# MultiVS.net
KiCad netlist of a schematic drawn in EAGLE
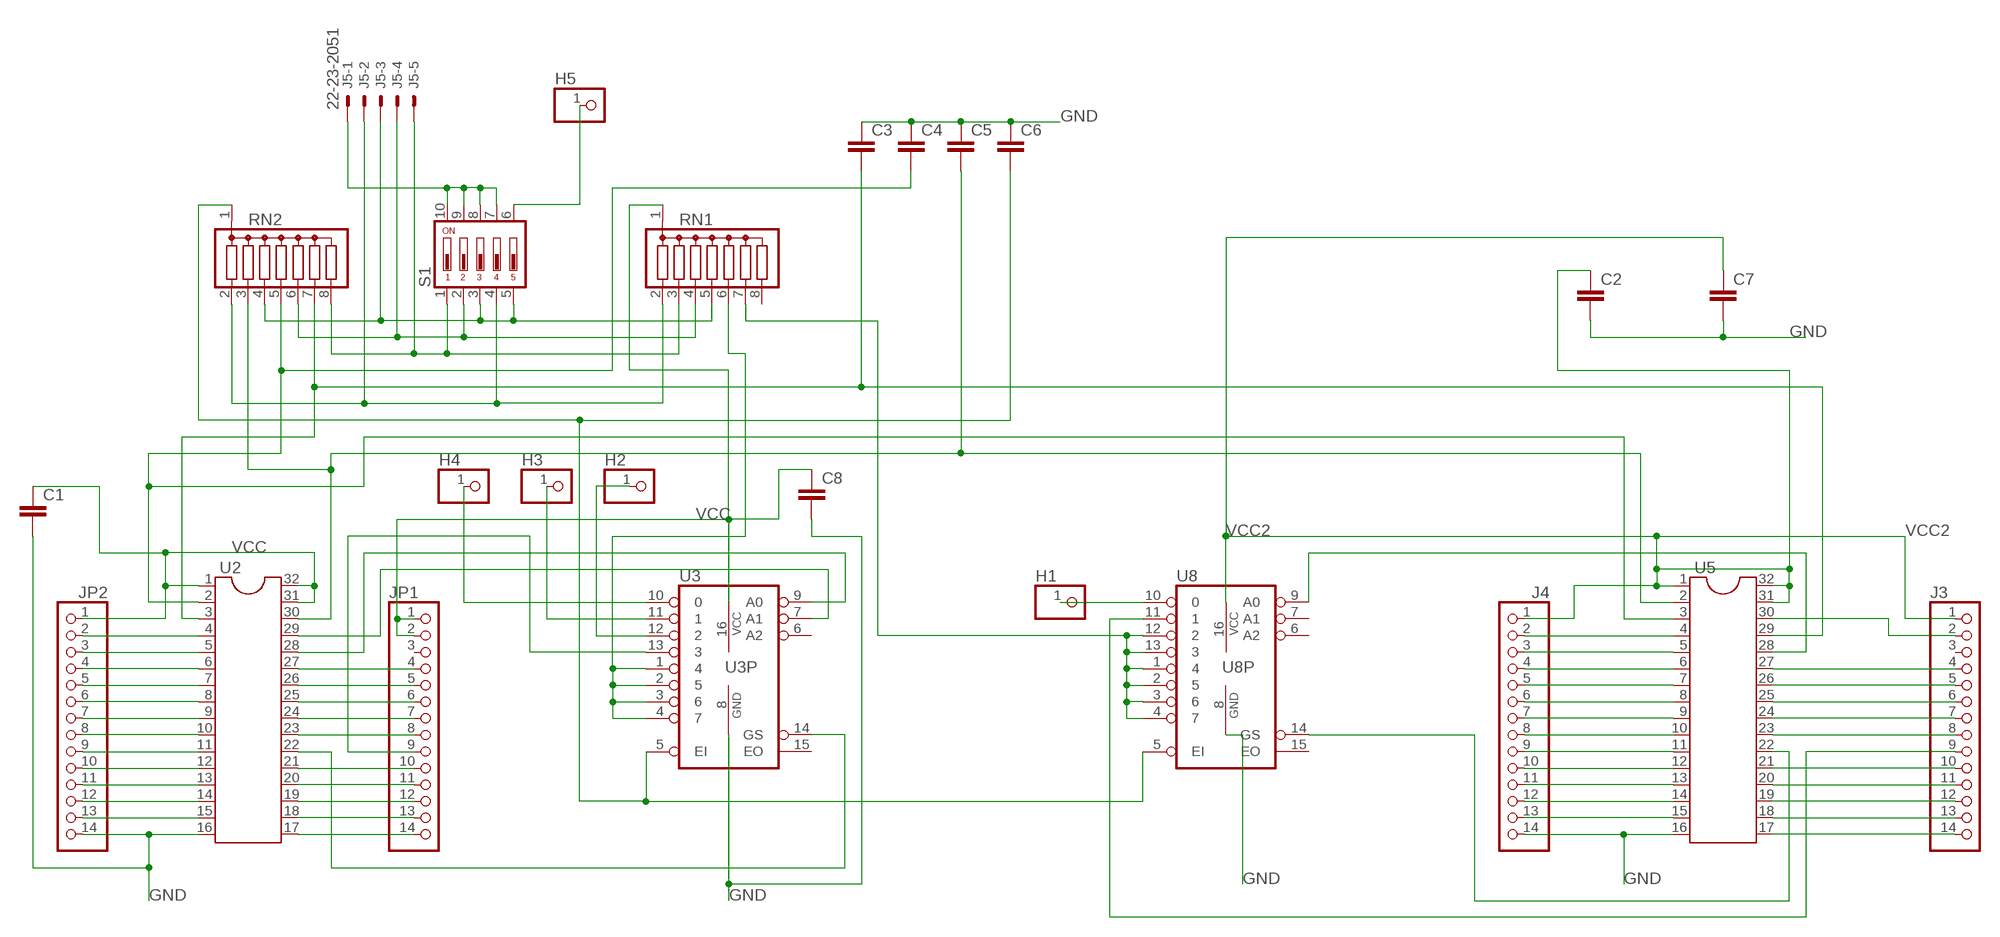
[diagram p0: schematic, sheet 1]

(export (version "E")
  (design (tool "Eeschema 10.0.6"))
  (components
    (comp (ref "C1")
      (value "C2.5/4")
      (footprint "eagle-import:C2.5-4")
      (libsource (lib "eagle-import") (part "C2.5/4"))
    )
    (comp (ref "C2")
      (value "C2.5/4")
      (footprint "eagle-import:C2.5-4")
      (libsource (lib "eagle-import") (part "C2.5/4"))
    )
    (comp (ref "C3")
      (value "C2.5/4")
      (footprint "eagle-import:C2.5-4")
      (libsource (lib "eagle-import") (part "C2.5/4"))
    )
    (comp (ref "C4")
      (value "C2.5/4")
      (footprint "eagle-import:C2.5-4")
      (libsource (lib "eagle-import") (part "C2.5/4"))
    )
    (comp (ref "C5")
      (value "C2.5/4")
      (footprint "eagle-import:C2.5-4")
      (libsource (lib "eagle-import") (part "C2.5/4"))
    )
    (comp (ref "C6")
      (value "C2.5/4")
      (footprint "eagle-import:C2.5-4")
      (libsource (lib "eagle-import") (part "C2.5/4"))
    )
    (comp (ref "C7")
      (value "C2.5/4")
      (footprint "eagle-import:C2.5-4")
      (libsource (lib "eagle-import") (part "C2.5/4"))
    )
    (comp (ref "C8")
      (value "C2.5/4")
      (footprint "eagle-import:C2.5-4")
      (libsource (lib "eagle-import") (part "C2.5/4"))
    )
    (comp (ref "H1")
      (value "PINHD-1X1")
      (footprint "eagle-import:1X01")
      (libsource (lib "eagle-import") (part "PINHD-1X1"))
    )
    (comp (ref "H2")
      (value "PINHD-1X1")
      (footprint "eagle-import:1X01")
      (libsource (lib "eagle-import") (part "PINHD-1X1"))
    )
    (comp (ref "H3")
      (value "PINHD-1X1")
      (footprint "eagle-import:1X01")
      (libsource (lib "eagle-import") (part "PINHD-1X1"))
    )
    (comp (ref "H4")
      (value "PINHD-1X1")
      (footprint "eagle-import:1X01")
      (libsource (lib "eagle-import") (part "PINHD-1X1"))
    )
    (comp (ref "H5")
      (value "PINHD-1X1")
      (footprint "eagle-import:1X01")
      (libsource (lib "eagle-import") (part "PINHD-1X1"))
    )
    (comp (ref "J3")
      (value "PINHD-1X14")
      (footprint "eagle-import:1X14")
      (libsource (lib "eagle-import") (part "PINHD-1X14"))
    )
    (comp (ref "J4")
      (value "PINHD-1X14")
      (footprint "eagle-import:1X14")
      (libsource (lib "eagle-import") (part "PINHD-1X14"))
    )
    (comp (ref "J5")
      (value "22-23-2051")
      (footprint "eagle-import:22-23-2051")
      (fields (field (name "MF") "MOLEX"))
      (libsource (lib "eagle-import") (part "22-23-2051"))
    )
    (comp (ref "JP1")
      (value "PINHD-1X14")
      (footprint "eagle-import:1X14")
      (libsource (lib "eagle-import") (part "PINHD-1X14"))
    )
    (comp (ref "JP2")
      (value "PINHD-1X14")
      (footprint "eagle-import:1X14")
      (libsource (lib "eagle-import") (part "PINHD-1X14"))
    )
    (comp (ref "RN1")
      (value "G07R")
      (footprint "eagle-import:SIL8")
      (libsource (lib "eagle-import") (part "G07R"))
    )
    (comp (ref "RN2")
      (value "G07R")
      (footprint "eagle-import:SIL8")
      (libsource (lib "eagle-import") (part "G07R"))
    )
    (comp (ref "S1")
      (value "DIP05YL")
      (footprint "eagle-import:DIP05YL")
      (libsource (lib "eagle-import") (part "DIP05YL"))
    )
    (comp (ref "U2")
      (value "DIL32")
      (footprint "eagle-import:DIL32")
      (libsource (lib "eagle-import") (part "DIL32"))
    )
    (comp (ref "U3")
      (value "74LS148N")
      (footprint "eagle-import:DIL16")
      (libsource (lib "eagle-import") (part "74148NLS"))
    )
    (comp (ref "U5")
      (value "DIL32")
      (footprint "eagle-import:DIL32")
      (libsource (lib "eagle-import") (part "DIL32"))
    )
    (comp (ref "U8")
      (value "74LS148N")
      (footprint "eagle-import:DIL16")
      (libsource (lib "eagle-import") (part "74148NLS"))
    )
  )
  (nets
    (net (code "1") (name "/GND") (class "Default")
      (node (ref "C1") (pin "2") (pinfunction "2_2") (pintype "passive"))
      (node (ref "C2") (pin "2") (pinfunction "2_2") (pintype "passive"))
      (node (ref "C3") (pin "1") (pinfunction "1_1") (pintype "passive"))
      (node (ref "C4") (pin "1") (pinfunction "1_1") (pintype "passive"))
      (node (ref "C5") (pin "1") (pinfunction "1_1") (pintype "passive"))
      (node (ref "C6") (pin "1") (pinfunction "1_1") (pintype "passive"))
      (node (ref "C7") (pin "2") (pinfunction "2_2") (pintype "passive"))
      (node (ref "C8") (pin "2") (pinfunction "2_2") (pintype "passive"))
      (node (ref "J4") (pin "14") (pinfunction "14_14") (pintype "passive"))
      (node (ref "JP2") (pin "14") (pinfunction "14_14") (pintype "passive"))
      (node (ref "U2") (pin "16") (pinfunction "16_16") (pintype "passive"))
      (node (ref "U3") (pin "8") (pinfunction "GND_8") (pintype "power_in"))
      (node (ref "U5") (pin "16") (pinfunction "16_16") (pintype "passive"))
      (node (ref "U8") (pin "8") (pinfunction "GND_8") (pintype "power_in"))
    )
    (net (code "2") (name "/VCC") (class "Default")
      (node (ref "C1") (pin "1") (pinfunction "1_1") (pintype "passive"))
      (node (ref "C8") (pin "1") (pinfunction "1_1") (pintype "passive"))
      (node (ref "JP1") (pin "1") (pinfunction "1_1") (pintype "passive"))
      (node (ref "JP1") (pin "2") (pinfunction "2_2") (pintype "passive"))
      (node (ref "JP2") (pin "1") (pinfunction "1_1") (pintype "passive"))
      (node (ref "RN1") (pin "1") (pinfunction "1_1") (pintype "passive"))
      (node (ref "U2") (pin "1") (pinfunction "1_1") (pintype "passive"))
      (node (ref "U2") (pin "31") (pinfunction "31_31") (pintype "passive"))
      (node (ref "U2") (pin "32") (pinfunction "32_32") (pintype "passive"))
      (node (ref "U3") (pin "16") (pinfunction "VCC_16") (pintype "power_in"))
    )
    (net (code "3") (name "/VCC2") (class "Default")
      (node (ref "C2") (pin "1") (pinfunction "1_1") (pintype "passive"))
      (node (ref "C7") (pin "1") (pinfunction "1_1") (pintype "passive"))
      (node (ref "J3") (pin "1") (pinfunction "1_1") (pintype "passive"))
      (node (ref "J4") (pin "1") (pinfunction "1_1") (pintype "passive"))
      (node (ref "U5") (pin "1") (pinfunction "1_1") (pintype "passive"))
      (node (ref "U5") (pin "31") (pinfunction "31_31") (pintype "passive"))
      (node (ref "U5") (pin "32") (pinfunction "32_32") (pintype "passive"))
      (node (ref "U8") (pin "16") (pinfunction "VCC_16") (pintype "power_in"))
    )
    (net (code "4") (name "Net-(C3-Pad2)") (class "Default")
      (node (ref "C3") (pin "2") (pinfunction "2_2") (pintype "passive"))
      (node (ref "RN2") (pin "7") (pinfunction "7_7") (pintype "passive"))
      (node (ref "U2") (pin "3") (pinfunction "3_3") (pintype "passive"))
      (node (ref "U5") (pin "29") (pinfunction "29_29") (pintype "passive"))
    )
    (net (code "5") (name "Net-(C4-Pad2)") (class "Default")
      (node (ref "C4") (pin "2") (pinfunction "2_2") (pintype "passive"))
      (node (ref "RN2") (pin "5") (pinfunction "5_5") (pintype "passive"))
      (node (ref "U2") (pin "2") (pinfunction "2_2") (pintype "passive"))
      (node (ref "U5") (pin "3") (pinfunction "3_3") (pintype "passive"))
    )
    (net (code "6") (name "Net-(C5-Pad2)") (class "Default")
      (node (ref "C5") (pin "2") (pinfunction "2_2") (pintype "passive"))
      (node (ref "RN2") (pin "3") (pinfunction "3_3") (pintype "passive"))
      (node (ref "U2") (pin "30") (pinfunction "30_30") (pintype "passive"))
      (node (ref "U5") (pin "2") (pinfunction "2_2") (pintype "passive"))
    )
    (net (code "7") (name "Net-(H5-Pad1)") (class "Default")
      (node (ref "H5") (pin "1") (pinfunction "1_1") (pintype "passive"))
      (node (ref "S1") (pin "6") (pinfunction "6_6") (pintype "passive"))
    )
    (net (code "8") (name "Net-(J3-Pad2)") (class "Default")
      (node (ref "J3") (pin "2") (pinfunction "2_2") (pintype "passive"))
      (node (ref "U5") (pin "30") (pinfunction "30_30") (pintype "passive"))
    )
    (net (code "9") (name "Net-(J3-Pad4)") (class "Default")
      (node (ref "J3") (pin "4") (pinfunction "4_4") (pintype "passive"))
      (node (ref "U5") (pin "27") (pinfunction "27_27") (pintype "passive"))
    )
    (net (code "10") (name "Net-(J3-Pad5)") (class "Default")
      (node (ref "J3") (pin "5") (pinfunction "5_5") (pintype "passive"))
      (node (ref "U5") (pin "26") (pinfunction "26_26") (pintype "passive"))
    )
    (net (code "11") (name "Net-(J3-Pad6)") (class "Default")
      (node (ref "J3") (pin "6") (pinfunction "6_6") (pintype "passive"))
      (node (ref "U5") (pin "25") (pinfunction "25_25") (pintype "passive"))
    )
    (net (code "12") (name "Net-(J3-Pad7)") (class "Default")
      (node (ref "J3") (pin "7") (pinfunction "7_7") (pintype "passive"))
      (node (ref "U5") (pin "24") (pinfunction "24_24") (pintype "passive"))
    )
    (net (code "13") (name "Net-(J3-Pad8)") (class "Default")
      (node (ref "J3") (pin "8") (pinfunction "8_8") (pintype "passive"))
      (node (ref "U5") (pin "23") (pinfunction "23_23") (pintype "passive"))
    )
    (net (code "14") (name "Net-(J3-Pad10)") (class "Default")
      (node (ref "J3") (pin "10") (pinfunction "10_10") (pintype "passive"))
      (node (ref "U5") (pin "21") (pinfunction "21_21") (pintype "passive"))
    )
    (net (code "15") (name "Net-(J3-Pad11)") (class "Default")
      (node (ref "J3") (pin "11") (pinfunction "11_11") (pintype "passive"))
      (node (ref "U5") (pin "20") (pinfunction "20_20") (pintype "passive"))
    )
    (net (code "16") (name "Net-(J3-Pad12)") (class "Default")
      (node (ref "J3") (pin "12") (pinfunction "12_12") (pintype "passive"))
      (node (ref "U5") (pin "19") (pinfunction "19_19") (pintype "passive"))
    )
    (net (code "17") (name "Net-(J3-Pad13)") (class "Default")
      (node (ref "J3") (pin "13") (pinfunction "13_13") (pintype "passive"))
      (node (ref "U5") (pin "18") (pinfunction "18_18") (pintype "passive"))
    )
    (net (code "18") (name "Net-(J3-Pad14)") (class "Default")
      (node (ref "J3") (pin "14") (pinfunction "14_14") (pintype "passive"))
      (node (ref "U5") (pin "17") (pinfunction "17_17") (pintype "passive"))
    )
    (net (code "19") (name "Net-(J4-Pad2)") (class "Default")
      (node (ref "J4") (pin "2") (pinfunction "2_2") (pintype "passive"))
      (node (ref "U5") (pin "4") (pinfunction "4_4") (pintype "passive"))
    )
    (net (code "20") (name "Net-(J4-Pad3)") (class "Default")
      (node (ref "J4") (pin "3") (pinfunction "3_3") (pintype "passive"))
      (node (ref "U5") (pin "5") (pinfunction "5_5") (pintype "passive"))
    )
    (net (code "21") (name "Net-(J4-Pad4)") (class "Default")
      (node (ref "J4") (pin "4") (pinfunction "4_4") (pintype "passive"))
      (node (ref "U5") (pin "6") (pinfunction "6_6") (pintype "passive"))
    )
    (net (code "22") (name "Net-(J4-Pad5)") (class "Default")
      (node (ref "J4") (pin "5") (pinfunction "5_5") (pintype "passive"))
      (node (ref "U5") (pin "7") (pinfunction "7_7") (pintype "passive"))
    )
    (net (code "23") (name "Net-(J4-Pad6)") (class "Default")
      (node (ref "J4") (pin "6") (pinfunction "6_6") (pintype "passive"))
      (node (ref "U5") (pin "8") (pinfunction "8_8") (pintype "passive"))
    )
    (net (code "24") (name "Net-(J4-Pad7)") (class "Default")
      (node (ref "J4") (pin "7") (pinfunction "7_7") (pintype "passive"))
      (node (ref "U5") (pin "9") (pinfunction "9_9") (pintype "passive"))
    )
    (net (code "25") (name "Net-(J4-Pad8)") (class "Default")
      (node (ref "J4") (pin "8") (pinfunction "8_8") (pintype "passive"))
      (node (ref "U5") (pin "10") (pinfunction "10_10") (pintype "passive"))
    )
    (net (code "26") (name "Net-(J4-Pad9)") (class "Default")
      (node (ref "J4") (pin "9") (pinfunction "9_9") (pintype "passive"))
      (node (ref "U5") (pin "11") (pinfunction "11_11") (pintype "passive"))
    )
    (net (code "27") (name "Net-(J4-Pad10)") (class "Default")
      (node (ref "J4") (pin "10") (pinfunction "10_10") (pintype "passive"))
      (node (ref "U5") (pin "12") (pinfunction "12_12") (pintype "passive"))
    )
    (net (code "28") (name "Net-(J4-Pad11)") (class "Default")
      (node (ref "J4") (pin "11") (pinfunction "11_11") (pintype "passive"))
      (node (ref "U5") (pin "13") (pinfunction "13_13") (pintype "passive"))
    )
    (net (code "29") (name "Net-(J4-Pad12)") (class "Default")
      (node (ref "J4") (pin "12") (pinfunction "12_12") (pintype "passive"))
      (node (ref "U5") (pin "14") (pinfunction "14_14") (pintype "passive"))
    )
    (net (code "30") (name "Net-(J4-Pad13)") (class "Default")
      (node (ref "J4") (pin "13") (pinfunction "13_13") (pintype "passive"))
      (node (ref "U5") (pin "15") (pinfunction "15_15") (pintype "passive"))
    )
    (net (code "31") (name "Net-(J5A-S)") (class "Default")
      (node (ref "J5") (pin "1") (pinfunction "S_1") (pintype "passive"))
      (node (ref "S1") (pin "10") (pinfunction "10_10") (pintype "passive"))
      (node (ref "S1") (pin "7") (pinfunction "7_7") (pintype "passive"))
      (node (ref "S1") (pin "8") (pinfunction "8_8") (pintype "passive"))
      (node (ref "S1") (pin "9") (pinfunction "9_9") (pintype "passive"))
    )
    (net (code "32") (name "Net-(J5B-S)") (class "Default")
      (node (ref "J5") (pin "2") (pinfunction "S_2") (pintype "passive"))
      (node (ref "RN1") (pin "2") (pinfunction "2_2") (pintype "passive"))
      (node (ref "RN2") (pin "2") (pinfunction "2_2") (pintype "passive"))
      (node (ref "S1") (pin "4") (pinfunction "4_4") (pintype "passive"))
    )
    (net (code "33") (name "Net-(J5C-S)") (class "Default")
      (node (ref "J5") (pin "3") (pinfunction "S_3") (pintype "passive"))
      (node (ref "RN1") (pin "5") (pinfunction "5_5") (pintype "passive"))
      (node (ref "RN2") (pin "4") (pinfunction "4_4") (pintype "passive"))
      (node (ref "S1") (pin "3") (pinfunction "3_3") (pintype "passive"))
      (node (ref "S1") (pin "5") (pinfunction "5_5") (pintype "passive"))
    )
    (net (code "34") (name "Net-(J5D-S)") (class "Default")
      (node (ref "J5") (pin "4") (pinfunction "S_4") (pintype "passive"))
      (node (ref "RN1") (pin "4") (pinfunction "4_4") (pintype "passive"))
      (node (ref "RN2") (pin "6") (pinfunction "6_6") (pintype "passive"))
      (node (ref "S1") (pin "2") (pinfunction "2_2") (pintype "passive"))
    )
    (net (code "35") (name "Net-(J5E-S)") (class "Default")
      (node (ref "J5") (pin "5") (pinfunction "S_5") (pintype "passive"))
      (node (ref "RN1") (pin "3") (pinfunction "3_3") (pintype "passive"))
      (node (ref "RN2") (pin "8") (pinfunction "8_8") (pintype "passive"))
      (node (ref "S1") (pin "1") (pinfunction "1_1") (pintype "passive"))
    )
    (net (code "36") (name "Net-(JP1-Pad4)") (class "Default")
      (node (ref "JP1") (pin "4") (pinfunction "4_4") (pintype "passive"))
      (node (ref "U2") (pin "27") (pinfunction "27_27") (pintype "passive"))
    )
    (net (code "37") (name "Net-(JP1-Pad5)") (class "Default")
      (node (ref "JP1") (pin "5") (pinfunction "5_5") (pintype "passive"))
      (node (ref "U2") (pin "26") (pinfunction "26_26") (pintype "passive"))
    )
    (net (code "38") (name "Net-(JP1-Pad6)") (class "Default")
      (node (ref "JP1") (pin "6") (pinfunction "6_6") (pintype "passive"))
      (node (ref "U2") (pin "25") (pinfunction "25_25") (pintype "passive"))
    )
    (net (code "39") (name "Net-(JP1-Pad7)") (class "Default")
      (node (ref "JP1") (pin "7") (pinfunction "7_7") (pintype "passive"))
      (node (ref "U2") (pin "24") (pinfunction "24_24") (pintype "passive"))
    )
    (net (code "40") (name "Net-(JP1-Pad8)") (class "Default")
      (node (ref "JP1") (pin "8") (pinfunction "8_8") (pintype "passive"))
      (node (ref "U2") (pin "23") (pinfunction "23_23") (pintype "passive"))
    )
    (net (code "41") (name "Net-(JP1-Pad10)") (class "Default")
      (node (ref "JP1") (pin "10") (pinfunction "10_10") (pintype "passive"))
      (node (ref "U2") (pin "21") (pinfunction "21_21") (pintype "passive"))
    )
    (net (code "42") (name "Net-(JP1-Pad11)") (class "Default")
      (node (ref "JP1") (pin "11") (pinfunction "11_11") (pintype "passive"))
      (node (ref "U2") (pin "20") (pinfunction "20_20") (pintype "passive"))
    )
    (net (code "43") (name "Net-(JP1-Pad12)") (class "Default")
      (node (ref "JP1") (pin "12") (pinfunction "12_12") (pintype "passive"))
      (node (ref "U2") (pin "19") (pinfunction "19_19") (pintype "passive"))
    )
    (net (code "44") (name "Net-(JP1-Pad13)") (class "Default")
      (node (ref "JP1") (pin "13") (pinfunction "13_13") (pintype "passive"))
      (node (ref "U2") (pin "18") (pinfunction "18_18") (pintype "passive"))
    )
    (net (code "45") (name "Net-(JP1-Pad14)") (class "Default")
      (node (ref "JP1") (pin "14") (pinfunction "14_14") (pintype "passive"))
      (node (ref "U2") (pin "17") (pinfunction "17_17") (pintype "passive"))
    )
    (net (code "46") (name "Net-(JP2-Pad2)") (class "Default")
      (node (ref "JP2") (pin "2") (pinfunction "2_2") (pintype "passive"))
      (node (ref "U2") (pin "4") (pinfunction "4_4") (pintype "passive"))
    )
    (net (code "47") (name "Net-(JP2-Pad3)") (class "Default")
      (node (ref "JP2") (pin "3") (pinfunction "3_3") (pintype "passive"))
      (node (ref "U2") (pin "5") (pinfunction "5_5") (pintype "passive"))
    )
    (net (code "48") (name "Net-(JP2-Pad4)") (class "Default")
      (node (ref "JP2") (pin "4") (pinfunction "4_4") (pintype "passive"))
      (node (ref "U2") (pin "6") (pinfunction "6_6") (pintype "passive"))
    )
    (net (code "49") (name "Net-(JP2-Pad5)") (class "Default")
      (node (ref "JP2") (pin "5") (pinfunction "5_5") (pintype "passive"))
      (node (ref "U2") (pin "7") (pinfunction "7_7") (pintype "passive"))
    )
    (net (code "50") (name "Net-(JP2-Pad6)") (class "Default")
      (node (ref "JP2") (pin "6") (pinfunction "6_6") (pintype "passive"))
      (node (ref "U2") (pin "8") (pinfunction "8_8") (pintype "passive"))
    )
    (net (code "51") (name "Net-(JP2-Pad7)") (class "Default")
      (node (ref "JP2") (pin "7") (pinfunction "7_7") (pintype "passive"))
      (node (ref "U2") (pin "9") (pinfunction "9_9") (pintype "passive"))
    )
    (net (code "52") (name "Net-(JP2-Pad8)") (class "Default")
      (node (ref "JP2") (pin "8") (pinfunction "8_8") (pintype "passive"))
      (node (ref "U2") (pin "10") (pinfunction "10_10") (pintype "passive"))
    )
    (net (code "53") (name "Net-(JP2-Pad9)") (class "Default")
      (node (ref "JP2") (pin "9") (pinfunction "9_9") (pintype "passive"))
      (node (ref "U2") (pin "11") (pinfunction "11_11") (pintype "passive"))
    )
    (net (code "54") (name "Net-(JP2-Pad10)") (class "Default")
      (node (ref "JP2") (pin "10") (pinfunction "10_10") (pintype "passive"))
      (node (ref "U2") (pin "12") (pinfunction "12_12") (pintype "passive"))
    )
    (net (code "55") (name "Net-(JP2-Pad11)") (class "Default")
      (node (ref "JP2") (pin "11") (pinfunction "11_11") (pintype "passive"))
      (node (ref "U2") (pin "13") (pinfunction "13_13") (pintype "passive"))
    )
    (net (code "56") (name "Net-(JP2-Pad12)") (class "Default")
      (node (ref "JP2") (pin "12") (pinfunction "12_12") (pintype "passive"))
      (node (ref "U2") (pin "14") (pinfunction "14_14") (pintype "passive"))
    )
    (net (code "57") (name "Net-(JP2-Pad13)") (class "Default")
      (node (ref "JP2") (pin "13") (pinfunction "13_13") (pintype "passive"))
      (node (ref "U2") (pin "15") (pinfunction "15_15") (pintype "passive"))
    )
    (net (code "58") (name "Net-(U3A-0)") (class "Default")
      (node (ref "H4") (pin "1") (pinfunction "1_1") (pintype "passive"))
      (node (ref "U3") (pin "10") (pinfunction "0_10") (pintype "input"))
    )
    (net (code "59") (name "Net-(U3A-1)") (class "Default")
      (node (ref "H3") (pin "1") (pinfunction "1_1") (pintype "passive"))
      (node (ref "U3") (pin "11") (pinfunction "1_11") (pintype "input"))
    )
    (net (code "60") (name "Net-(U3A-2)") (class "Default")
      (node (ref "H2") (pin "1") (pinfunction "1_1") (pintype "passive"))
      (node (ref "U3") (pin "12") (pinfunction "2_12") (pintype "input"))
    )
    (net (code "61") (name "Net-(U3A-3)") (class "Default")
      (node (ref "JP1") (pin "9") (pinfunction "9_9") (pintype "passive"))
      (node (ref "U3") (pin "13") (pinfunction "3_13") (pintype "input"))
    )
    (net (code "62") (name "Net-(U3A-4)") (class "Default")
      (node (ref "RN1") (pin "6") (pinfunction "6_6") (pintype "passive"))
      (node (ref "U3") (pin "1") (pinfunction "4_1") (pintype "input"))
      (node (ref "U3") (pin "2") (pinfunction "5_2") (pintype "input"))
      (node (ref "U3") (pin "3") (pinfunction "6_3") (pintype "input"))
      (node (ref "U3") (pin "4") (pinfunction "7_4") (pintype "input"))
    )
    (net (code "63") (name "Net-(U3A-A0)") (class "Default")
      (node (ref "U2") (pin "28") (pinfunction "28_28") (pintype "passive"))
      (node (ref "U3") (pin "9") (pinfunction "A0_9") (pintype "output"))
    )
    (net (code "64") (name "Net-(U3A-A1)") (class "Default")
      (node (ref "U2") (pin "29") (pinfunction "29_29") (pintype "passive"))
      (node (ref "U3") (pin "7") (pinfunction "A1_7") (pintype "output"))
    )
    (net (code "65") (name "Net-(U3A-EI)") (class "Default")
      (node (ref "C6") (pin "2") (pinfunction "2_2") (pintype "passive"))
      (node (ref "RN2") (pin "1") (pinfunction "1_1") (pintype "passive"))
      (node (ref "U3") (pin "5") (pinfunction "EI_5") (pintype "input"))
      (node (ref "U8") (pin "5") (pinfunction "EI_5") (pintype "input"))
    )
    (net (code "66") (name "Net-(U3A-GS)") (class "Default")
      (node (ref "U2") (pin "22") (pinfunction "22_22") (pintype "passive"))
      (node (ref "U3") (pin "14") (pinfunction "GS_14") (pintype "output"))
    )
    (net (code "67") (name "Net-(U8A-0)") (class "Default")
      (node (ref "H1") (pin "1") (pinfunction "1_1") (pintype "passive"))
      (node (ref "U8") (pin "10") (pinfunction "0_10") (pintype "input"))
    )
    (net (code "68") (name "Net-(U8A-1)") (class "Default")
      (node (ref "J3") (pin "9") (pinfunction "9_9") (pintype "passive"))
      (node (ref "U8") (pin "11") (pinfunction "1_11") (pintype "input"))
    )
    (net (code "69") (name "Net-(U8A-2)") (class "Default")
      (node (ref "RN1") (pin "7") (pinfunction "7_7") (pintype "passive"))
      (node (ref "U8") (pin "1") (pinfunction "4_1") (pintype "input"))
      (node (ref "U8") (pin "12") (pinfunction "2_12") (pintype "input"))
      (node (ref "U8") (pin "13") (pinfunction "3_13") (pintype "input"))
      (node (ref "U8") (pin "2") (pinfunction "5_2") (pintype "input"))
      (node (ref "U8") (pin "3") (pinfunction "6_3") (pintype "input"))
      (node (ref "U8") (pin "4") (pinfunction "7_4") (pintype "input"))
    )
    (net (code "70") (name "Net-(U8A-A0)") (class "Default")
      (node (ref "U5") (pin "28") (pinfunction "28_28") (pintype "passive"))
      (node (ref "U8") (pin "9") (pinfunction "A0_9") (pintype "output"))
    )
    (net (code "71") (name "Net-(U8A-GS)") (class "Default")
      (node (ref "U5") (pin "22") (pinfunction "22_22") (pintype "passive"))
      (node (ref "U8") (pin "14") (pinfunction "GS_14") (pintype "output"))
    )
    (net (code "72") (name "unconnected-(J3-Pad3)") (class "Default")
      (node (ref "J3") (pin "3") (pinfunction "3_3") (pintype "passive"))
    )
    (net (code "73") (name "unconnected-(JP1-Pad3)") (class "Default")
      (node (ref "JP1") (pin "3") (pinfunction "3_3") (pintype "passive"))
    )
    (net (code "74") (name "unconnected-(RN1-Pad8)") (class "Default")
      (node (ref "RN1") (pin "8") (pinfunction "8_8") (pintype "passive"))
    )
    (net (code "75") (name "unconnected-(U3A-A2-Pad6)") (class "Default")
      (node (ref "U3") (pin "6") (pinfunction "A2_6") (pintype "output"))
    )
    (net (code "76") (name "unconnected-(U3A-EO-Pad15)") (class "Default")
      (node (ref "U3") (pin "15") (pinfunction "EO_15") (pintype "output"))
    )
    (net (code "77") (name "unconnected-(U8A-A1-Pad7)") (class "Default")
      (node (ref "U8") (pin "7") (pinfunction "A1_7") (pintype "output"))
    )
    (net (code "78") (name "unconnected-(U8A-A2-Pad6)") (class "Default")
      (node (ref "U8") (pin "6") (pinfunction "A2_6") (pintype "output"))
    )
    (net (code "79") (name "unconnected-(U8A-EO-Pad15)") (class "Default")
      (node (ref "U8") (pin "15") (pinfunction "EO_15") (pintype "output"))
    )
  )
)
